# LC_LPF1.net
KiCad netlist of a schematic drawn in Altium Designer
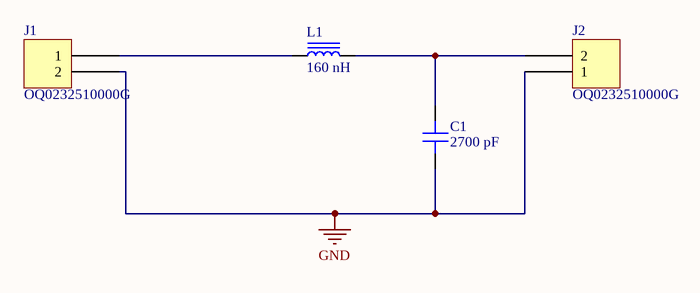
[diagram p0: LC_LPF1.SchDoc]

(export (version "E")
  (design (tool "Eeschema 10.0.6"))
  (components
    (comp (ref "C1")
      (value "2700 pF")
      (footprint "CAP 0603_1608")
      (description "CAP CER 2700PF 25V NP0 0603")
      (fields (field (name "PART NUMBER") "C0603C272F3GAC7867") (field (name "MANUFACTURER") "KEMET"))
      (libsource (lib "Celestial Altium Library - altium_library") (part "Capacitor"))
    )
    (comp (ref "J1")
      (value "OQ0232510000G")
      (footprint "FCI 06-381-2PIN")
      (description "TERM BLOCK HDR 2POS 90DEG 3.81MM")
      (fields (field (name "MANUFACTURER") "Amphenol Anytek"))
      (libsource (lib "Celestial Altium Library - altium_library") (part "2 Pin"))
    )
    (comp (ref "J2")
      (value "OQ0232510000G")
      (footprint "FCI 06-381-2PIN")
      (description "TERM BLOCK HDR 2POS 90DEG 3.81MM")
      (fields (field (name "MANUFACTURER") "Amphenol Anytek"))
      (libsource (lib "") (part "2 Pin_1"))
    )
    (comp (ref "L1")
      (value "160 nH")
      (footprint "IND 0402_1005 RF WW")
      (description "FIXED IND 160NH 480MA 330MOHM SM")
      (fields
        (field (name "PART NUMBER") "LQW15CNR16J00D")
        (field (name "MANUFACTURER") "Murata Electronics")
      )
      (libsource (lib "Celestial Altium Library - altium_library") (part "Inductor"))
    )
  )
  (nets
    (net (code "1") (name "GND") (class "Default")
      (node (ref "C1") (pin "1") (pinfunction "1_1") (pintype "passive"))
      (node (ref "J1") (pin "2") (pinfunction "2_2") (pintype "passive"))
      (node (ref "J2") (pin "1") (pinfunction "1_1") (pintype "passive"))
    )
    (net (code "2") (name "Net-(C1-Pad2)") (class "Default")
      (node (ref "C1") (pin "2") (pinfunction "2_2") (pintype "passive"))
      (node (ref "J2") (pin "2") (pinfunction "2_2") (pintype "passive"))
      (node (ref "L1") (pin "2") (pinfunction "2_2") (pintype "passive"))
    )
    (net (code "3") (name "Net-(J1-Pad1)") (class "Default")
      (node (ref "J1") (pin "1") (pinfunction "1_1") (pintype "passive"))
      (node (ref "L1") (pin "1") (pinfunction "1_1") (pintype "passive"))
    )
  )
)
